# batteryholder2S4P_revD.net
KiCad netlist of a schematic drawn in EAGLE
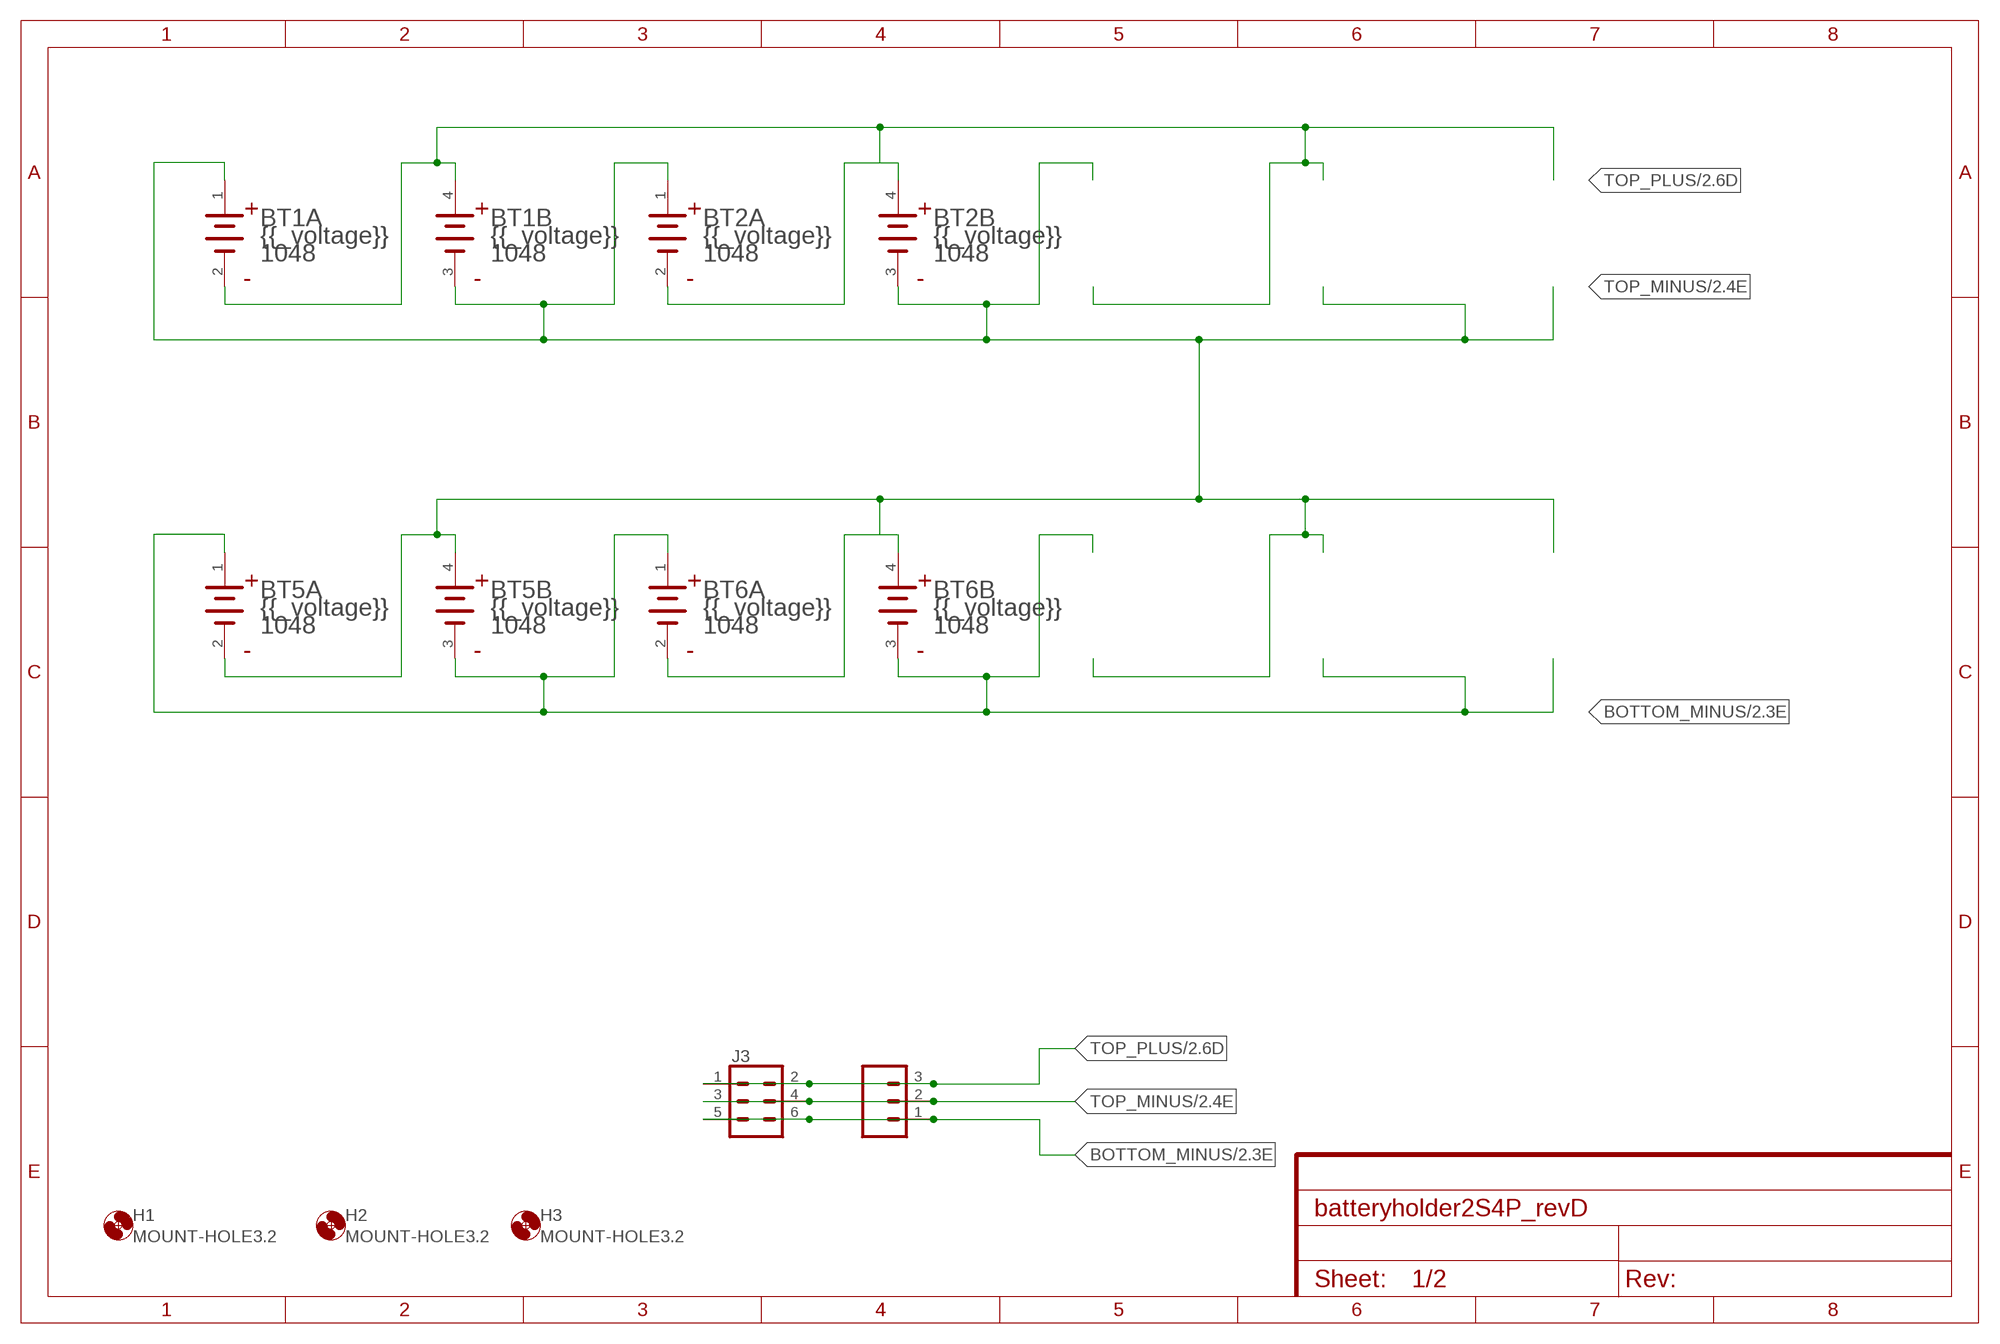
[diagram p0: schematic, sheet 1]
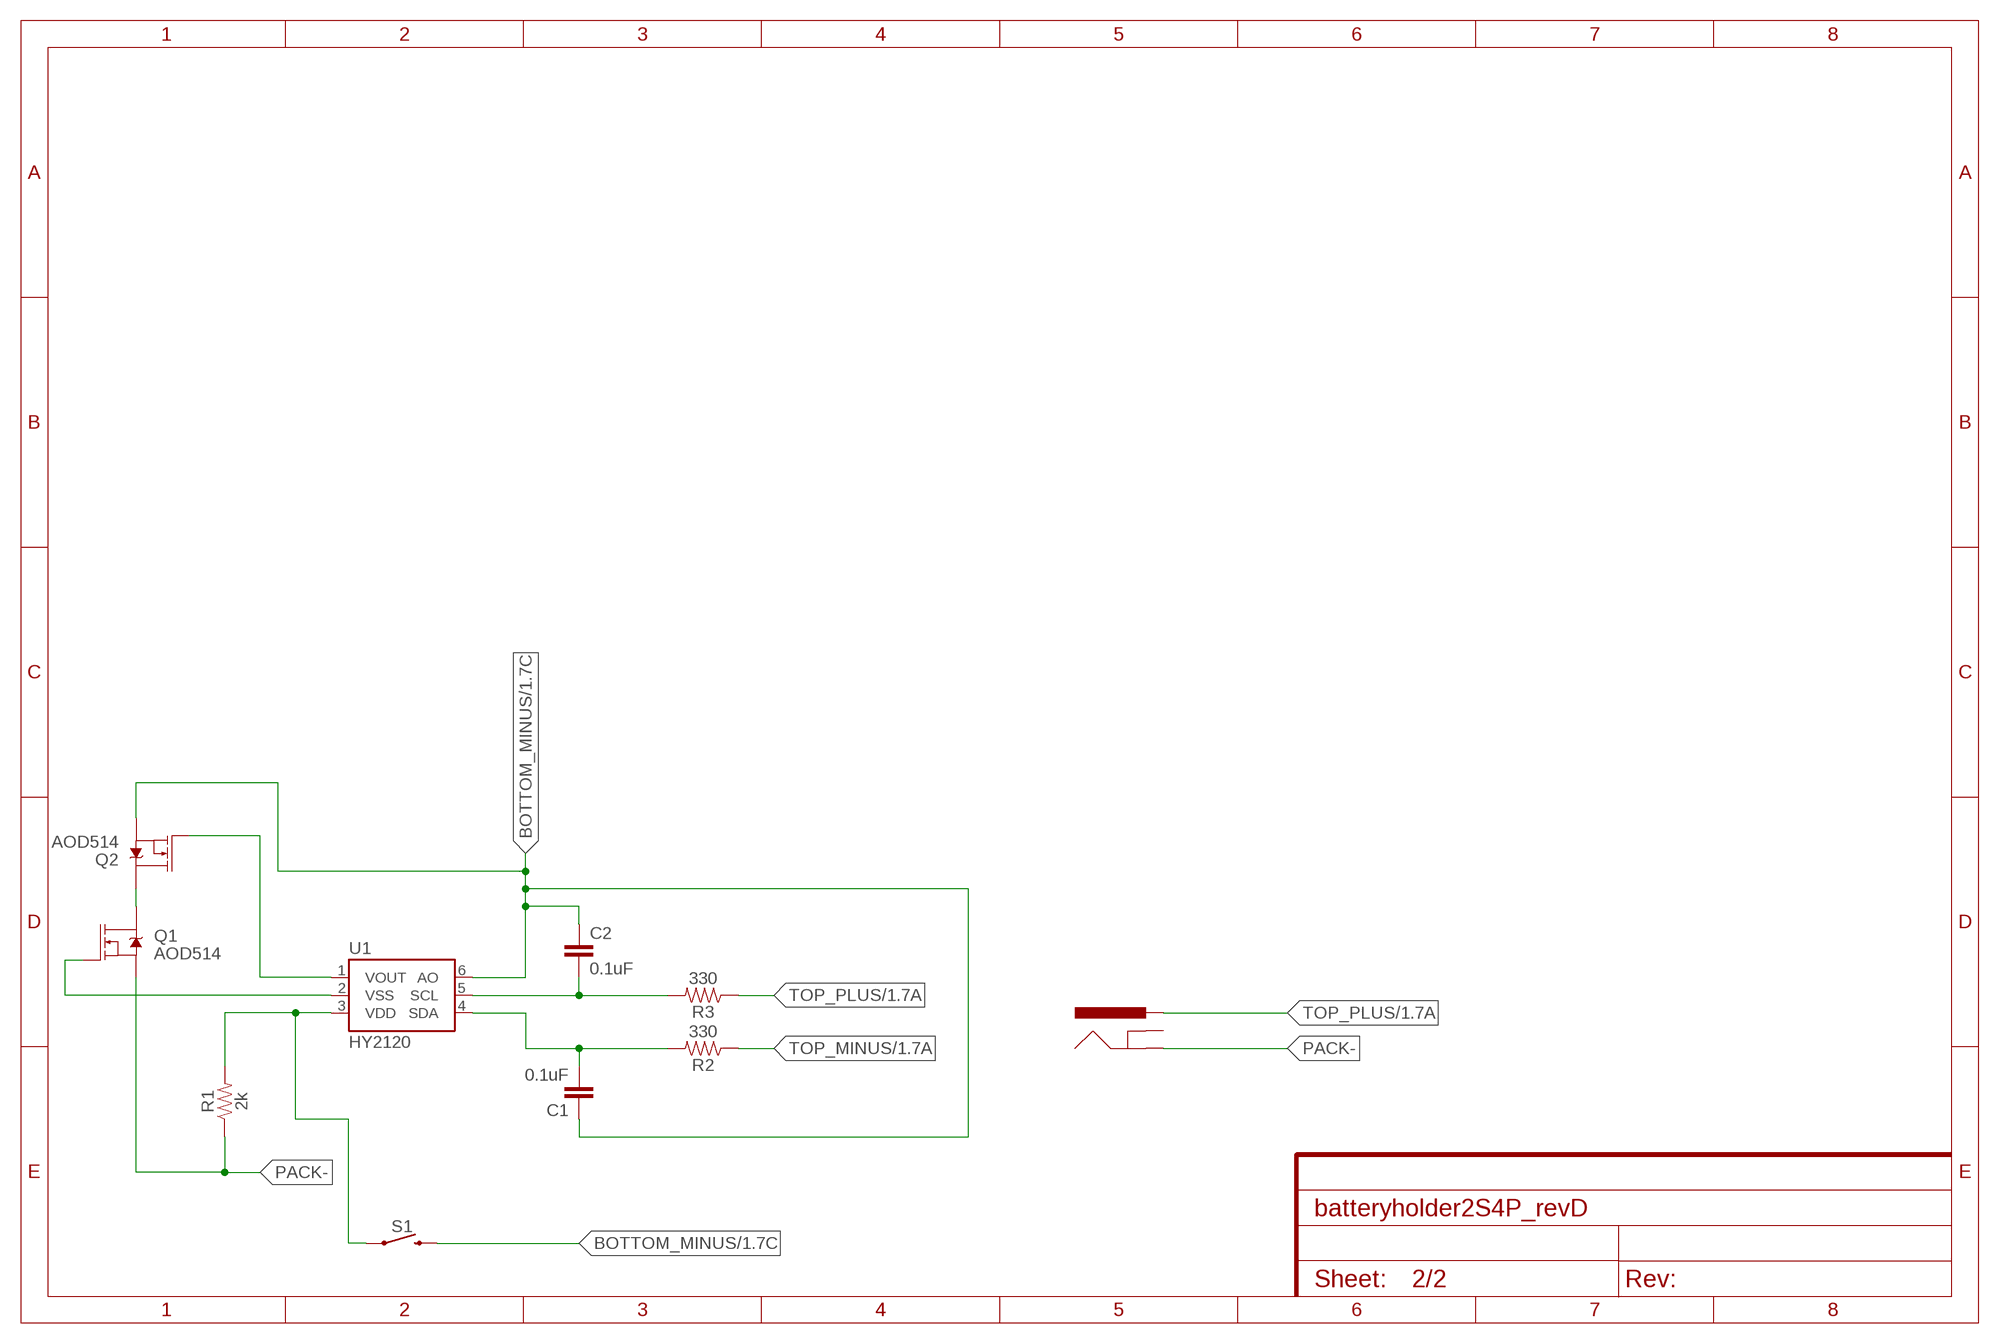
[diagram p1: schematic, sheet 2]

(export (version "E")
  (design (tool "Eeschema 10.0.6"))
  (components
    (comp (ref "BT1")
      (value "KEYSTONE_1048KEYSTONE_1048_0_0")
      (footprint "eagle-import:KEYSTONE_1048_0")
      (fields
        (field (name "DIGIKEY_PART_NUMBER") "36-1048-ND")
        (field (name "MF") "Keystone")
        (field (name "MOUSER_PART_NUMBER") "534-1048")
      )
      (libsource (lib "eagle-import") (part "KEYSTONE_1048KEYSTONE_1048_0_0"))
    )
    (comp (ref "BT2")
      (value "KEYSTONE_1048KEYSTONE_1048_0_0")
      (footprint "eagle-import:KEYSTONE_1048_0")
      (fields
        (field (name "DIGIKEY_PART_NUMBER") "36-1048-ND")
        (field (name "MF") "Keystone")
        (field (name "MOUSER_PART_NUMBER") "534-1048")
      )
      (libsource (lib "eagle-import") (part "KEYSTONE_1048KEYSTONE_1048_0_0"))
    )
    (comp (ref "BT5")
      (value "KEYSTONE_1048KEYSTONE_1048_0_0")
      (footprint "eagle-import:KEYSTONE_1048_0")
      (fields
        (field (name "DIGIKEY_PART_NUMBER") "36-1048-ND")
        (field (name "MF") "Keystone")
        (field (name "MOUSER_PART_NUMBER") "534-1048")
      )
      (libsource (lib "eagle-import") (part "KEYSTONE_1048KEYSTONE_1048_0_0"))
    )
    (comp (ref "BT6")
      (value "KEYSTONE_1048KEYSTONE_1048_0_0")
      (footprint "eagle-import:KEYSTONE_1048_0")
      (fields
        (field (name "DIGIKEY_PART_NUMBER") "36-1048-ND")
        (field (name "MF") "Keystone")
        (field (name "MOUSER_PART_NUMBER") "534-1048")
      )
      (libsource (lib "eagle-import") (part "KEYSTONE_1048KEYSTONE_1048_0_0"))
    )
    (comp (ref "H1")
      (value "MOUNT-HOLE3.2")
      (footprint "eagle-import:3,2")
      (libsource (lib "eagle-import") (part "MOUNT-HOLE3.2"))
    )
    (comp (ref "H2")
      (value "MOUNT-HOLE3.2")
      (footprint "eagle-import:3,2")
      (libsource (lib "eagle-import") (part "MOUNT-HOLE3.2"))
    )
    (comp (ref "H3")
      (value "MOUNT-HOLE3.2")
      (footprint "eagle-import:3,2")
      (libsource (lib "eagle-import") (part "MOUNT-HOLE3.2"))
    )
    (comp (ref "J1")
      (value "CONN_03-SCREW-5MM")
      (footprint "eagle-import:SCREWTERMINAL-5MM-3")
      (libsource (lib "eagle-import") (part "CONN_03-SCREW-5MM"))
    )
    (comp (ref "J3")
      (value "CONN_03X2SHROUD")
      (footprint "eagle-import:2X3-SHROUDED")
      (libsource (lib "eagle-import") (part "CONN_03X2SHROUD"))
    )
    (comp (ref "C1")
      (value "0.1uF")
      (footprint "eagle-import:1206")
      (libsource (lib "eagle-import") (part "1.0UF-1206-50V-10%"))
    )
    (comp (ref "C2")
      (value "0.1uF")
      (footprint "eagle-import:1206")
      (libsource (lib "eagle-import") (part "1.0UF-1206-50V-10%"))
    )
    (comp (ref "J2")
      (value "POWER_JACKPTH_BREAD")
      (footprint "eagle-import:POWER_JACK_PTH_BREAD")
      (libsource (lib "eagle-import") (part "POWER_JACKPTH_BREAD"))
    )
    (comp (ref "Q1")
      (value "AOD514")
      (footprint "eagle-import:DPAK")
      (libsource (lib "eagle-import") (part "MOSFET-NCH-FDD8780"))
    )
    (comp (ref "Q2")
      (value "AOD514")
      (footprint "eagle-import:DPAK")
      (libsource (lib "eagle-import") (part "MOSFET-NCH-FDD8780"))
    )
    (comp (ref "R1")
      (value "2k")
      (footprint "eagle-import:1206")
      (libsource (lib "eagle-import") (part "RESISTOR1206"))
    )
    (comp (ref "R2")
      (value "330")
      (footprint "eagle-import:1206")
      (libsource (lib "eagle-import") (part "RESISTOR1206"))
    )
    (comp (ref "R3")
      (value "330")
      (footprint "eagle-import:1206")
      (libsource (lib "eagle-import") (part "RESISTOR1206"))
    )
    (comp (ref "S1")
      (value "MOMENTARY-SWITCH-SPST-PTH-6.0MM")
      (footprint "eagle-import:TACTILE_SWITCH_PTH_6.0MM")
      (libsource (lib "eagle-import") (part "MOMENTARY-SWITCH-SPST-PTH-6.0MM"))
    )
    (comp (ref "U1")
      (value "HY2120")
      (footprint "eagle-import:SOT23-6")
      (libsource (lib "eagle-import") (part "MCP4725SOT-23"))
    )
  )
  (nets
    (net (code "1") (name "BOTTOM_MINUS") (class "Default")
      (node (ref "BT5") (pin "1") (pinfunction "1_ANODE_1") (pintype "passive"))
      (node (ref "BT5") (pin "3") (pinfunction "2_CATHODE_3") (pintype "passive"))
      (node (ref "BT6") (pin "1") (pinfunction "1_ANODE_1") (pintype "passive"))
      (node (ref "BT6") (pin "3") (pinfunction "2_CATHODE_3") (pintype "passive"))
      (node (ref "C1") (pin "1") (pinfunction "1_1") (pintype "passive"))
      (node (ref "C2") (pin "1") (pinfunction "1_1") (pintype "passive"))
      (node (ref "J1") (pin "1") (pinfunction "1_1") (pintype "passive"))
      (node (ref "J3") (pin "5") (pinfunction "5_5") (pintype "bidirectional"))
      (node (ref "J3") (pin "6") (pinfunction "6_6") (pintype "bidirectional"))
      (node (ref "Q2") (pin "3") (pinfunction "S_3") (pintype "bidirectional"))
      (node (ref "S1") (pin "3") (pinfunction "2_3") (pintype "passive"))
      (node (ref "U1") (pin "6") (pinfunction "AO_6") (pintype "bidirectional"))
    )
    (net (code "2") (name "Net-(Q1-D)") (class "Default")
      (node (ref "Q1") (pin "4") (pinfunction "D_4") (pintype "bidirectional"))
      (node (ref "Q2") (pin "4") (pinfunction "D_4") (pintype "bidirectional"))
    )
    (net (code "3") (name "Net-(Q1-G)") (class "Default")
      (node (ref "Q1") (pin "1") (pinfunction "G_1") (pintype "bidirectional"))
      (node (ref "U1") (pin "2") (pinfunction "VSS_2") (pintype "bidirectional"))
    )
    (net (code "4") (name "Net-(Q2-G)") (class "Default")
      (node (ref "Q2") (pin "1") (pinfunction "G_1") (pintype "bidirectional"))
      (node (ref "U1") (pin "1") (pinfunction "VOUT_1") (pintype "bidirectional"))
    )
    (net (code "5") (name "Net-(U1-SCL)") (class "Default")
      (node (ref "C2") (pin "2") (pinfunction "2_2") (pintype "passive"))
      (node (ref "R3") (pin "2") (pinfunction "2_2") (pintype "passive"))
      (node (ref "U1") (pin "5") (pinfunction "SCL_5") (pintype "bidirectional"))
    )
    (net (code "6") (name "Net-(U1-SDA)") (class "Default")
      (node (ref "C1") (pin "2") (pinfunction "2_2") (pintype "passive"))
      (node (ref "R2") (pin "2") (pinfunction "2_2") (pintype "passive"))
      (node (ref "U1") (pin "4") (pinfunction "SDA_4") (pintype "bidirectional"))
    )
    (net (code "7") (name "Net-(U1-VDD)") (class "Default")
      (node (ref "R1") (pin "2") (pinfunction "2_2") (pintype "passive"))
      (node (ref "S1") (pin "1") (pinfunction "1_1") (pintype "passive"))
      (node (ref "U1") (pin "3") (pinfunction "VDD_3") (pintype "bidirectional"))
    )
    (net (code "8") (name "PACK-") (class "Default")
      (node (ref "J2") (pin "GND") (pinfunction "GND_GND") (pintype "bidirectional"))
      (node (ref "Q1") (pin "3") (pinfunction "S_3") (pintype "bidirectional"))
      (node (ref "R1") (pin "1") (pinfunction "1_1") (pintype "passive"))
    )
    (net (code "9") (name "TOP_MINUS") (class "Default")
      (node (ref "BT1") (pin "1") (pinfunction "1_ANODE_1") (pintype "passive"))
      (node (ref "BT1") (pin "3") (pinfunction "2_CATHODE_3") (pintype "passive"))
      (node (ref "BT2") (pin "1") (pinfunction "1_ANODE_1") (pintype "passive"))
      (node (ref "BT2") (pin "3") (pinfunction "2_CATHODE_3") (pintype "passive"))
      (node (ref "BT5") (pin "2") (pinfunction "1_CATHODE_2") (pintype "passive"))
      (node (ref "BT5") (pin "4") (pinfunction "2_ANODE_4") (pintype "passive"))
      (node (ref "BT6") (pin "2") (pinfunction "1_CATHODE_2") (pintype "passive"))
      (node (ref "BT6") (pin "4") (pinfunction "2_ANODE_4") (pintype "passive"))
      (node (ref "J1") (pin "2") (pinfunction "2_2") (pintype "passive"))
      (node (ref "J3") (pin "3") (pinfunction "3_3") (pintype "bidirectional"))
      (node (ref "J3") (pin "4") (pinfunction "4_4") (pintype "bidirectional"))
      (node (ref "R2") (pin "1") (pinfunction "1_1") (pintype "passive"))
    )
    (net (code "10") (name "TOP_PLUS") (class "Default")
      (node (ref "BT1") (pin "2") (pinfunction "1_CATHODE_2") (pintype "passive"))
      (node (ref "BT1") (pin "4") (pinfunction "2_ANODE_4") (pintype "passive"))
      (node (ref "BT2") (pin "2") (pinfunction "1_CATHODE_2") (pintype "passive"))
      (node (ref "BT2") (pin "4") (pinfunction "2_ANODE_4") (pintype "passive"))
      (node (ref "J1") (pin "3") (pinfunction "3_3") (pintype "passive"))
      (node (ref "J2") (pin "PWR") (pinfunction "PWR_PWR") (pintype "bidirectional"))
      (node (ref "J3") (pin "1") (pinfunction "1_1") (pintype "bidirectional"))
      (node (ref "J3") (pin "2") (pinfunction "2_2") (pintype "bidirectional"))
      (node (ref "R3") (pin "1") (pinfunction "1_1") (pintype "passive"))
    )
    (net (code "11") (name "unconnected-(J2-PadGNDBREAK)") (class "Default")
      (node (ref "J2") (pin "GNDBREAK") (pinfunction "GNDBREAK_GNDBREAK") (pintype "bidirectional"))
    )
  )
)
